# MRCS-Buckeroo.net
KiCad netlist of a schematic drawn in EAGLE
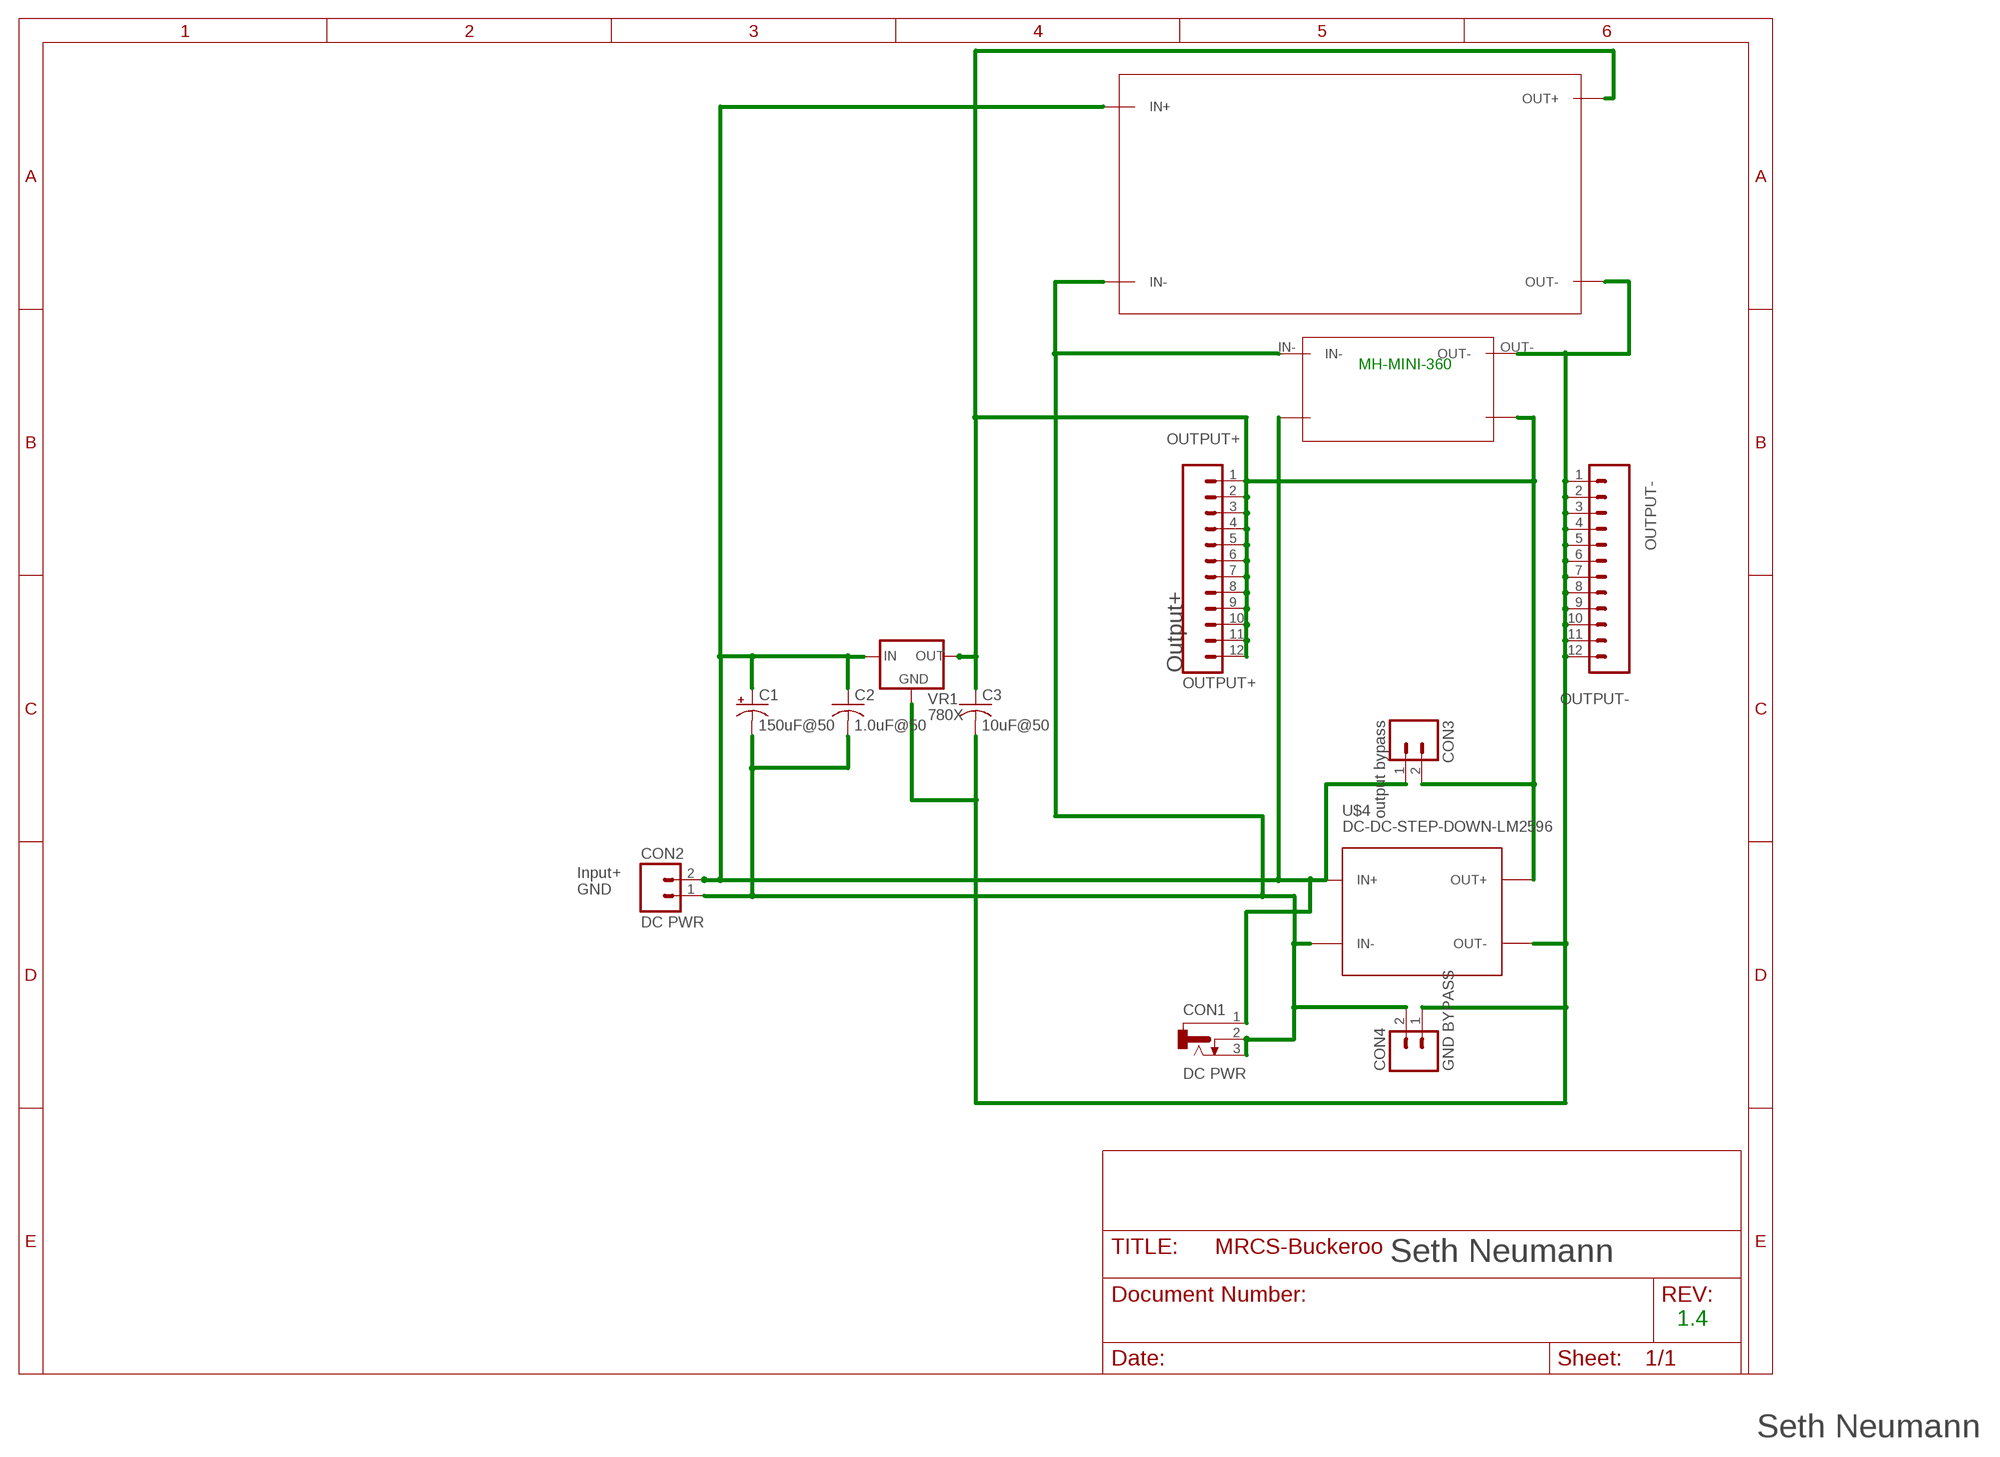
[diagram p0: schematic, sheet 1]

(export (version "E")
  (design (tool "Eeschema 10.0.6"))
  (components
    (comp (ref "C1")
      (value "150uF@50")
      (footprint "eagle-import:E5-10.5")
      (libsource (lib "eagle-import") (part "CAP-POLPTH-5MM"))
    )
    (comp (ref "C2")
      (value "1.0uF@50")
      (footprint "eagle-import:C-PTH-0.100")
      (libsource (lib "eagle-import") (part "CAPPTH2"))
    )
    (comp (ref "C3")
      (value "10uF@50")
      (footprint "eagle-import:C-PTH-0.100")
      (libsource (lib "eagle-import") (part "CAPPTH2"))
    )
    (comp (ref "CON1")
      (value "DC PWR")
      (footprint "eagle-import:DCJ0202")
      (libsource (lib "eagle-import") (part "CONNECTOR-DC-POWER-RA"))
    )
    (comp (ref "CON2")
      (value "DC PWR")
      (footprint "eagle-import:SCREWTERMINAL-3.5MM-2_LOCK")
      (libsource (lib "eagle-import") (part "CONNECTOR-M023.5MM-LOCK"))
    )
    (comp (ref "CON3")
      (value "output bypass")
      (footprint "eagle-import:MOLEX-1X2_LOCK")
      (libsource (lib "eagle-import") (part "CONNECTOR-M02MOLEX-1X02-LOCK"))
    )
    (comp (ref "CON4")
      (value "GND BYPASS")
      (footprint "eagle-import:MOLEX-1X2_LOCK")
      (libsource (lib "eagle-import") (part "CONNECTOR-M02MOLEX-1X02-LOCK"))
    )
    (comp (ref "MH-MINI-360")
      (value "MH-MINI-360")
      (footprint "eagle-import:MH-MINI-360")
      (libsource (lib "eagle-import") (part "MH-MINI-360"))
    )
    (comp (ref "OUTPUT+")
      (value "OUTPUT+")
      (footprint "eagle-import:1X12_LOCK")
      (libsource (lib "eagle-import") (part "CONNECTOR-M12LOCK"))
    )
    (comp (ref "OUTPUT-")
      (value "OUTPUT-")
      (footprint "eagle-import:1X12_LOCK")
      (libsource (lib "eagle-import") (part "CONNECTOR-M12LOCK"))
    )
    (comp (ref "U$4")
      (value "DC-DC-STEP-DOWN-LM2596")
      (footprint "eagle-import:DC-DC-STEP-DOWN-LM2596")
      (libsource (lib "eagle-import") (part "DC-DC-STEP-DOWN-LM2596"))
    )
    (comp (ref "U$5")
      (value "XL6009BOARD")
      (footprint "eagle-import:XL6009_BOARD")
      (libsource (lib "eagle-import") (part "XL6009BOARD"))
    )
    (comp (ref "VR1")
      (value "780X")
      (footprint "eagle-import:TO-220-RA")
      (libsource (lib "eagle-import") (part "VREG-?-PTH-RA"))
    )
  )
  (nets
    (net (code "1") (name "Net-(CON2-A)") (class "Default")
      (node (ref "C1") (pin "-") (pinfunction "-_-") (pintype "passive"))
      (node (ref "C2") (pin "2") (pinfunction "2_2") (pintype "passive"))
      (node (ref "CON1") (pin "2") (pinfunction "2_2") (pintype "passive"))
      (node (ref "CON1") (pin "3") (pinfunction "3_3") (pintype "passive"))
      (node (ref "CON2") (pin "1") (pinfunction "A_1") (pintype "passive"))
      (node (ref "CON4") (pin "2") (pinfunction "B_2") (pintype "passive"))
      (node (ref "MH-MINI-360") (pin "IN-") (pinfunction "IN-_IN-") (pintype "bidirectional"))
      (node (ref "U$4") (pin "IN-") (pinfunction "IN-_IN-") (pintype "bidirectional"))
      (node (ref "U$5") (pin "IN-") (pinfunction "IN-_IN-") (pintype "bidirectional"))
    )
    (net (code "2") (name "Net-(CON2-B)") (class "Default")
      (node (ref "C1") (pin "+") (pinfunction "+_+") (pintype "passive"))
      (node (ref "C2") (pin "1") (pinfunction "1_1") (pintype "passive"))
      (node (ref "CON1") (pin "1") (pinfunction "1_1") (pintype "passive"))
      (node (ref "CON2") (pin "2") (pinfunction "B_2") (pintype "passive"))
      (node (ref "CON3") (pin "1") (pinfunction "A_1") (pintype "passive"))
      (node (ref "MH-MINI-360") (pin "INN+") (pinfunction "INN+_INN+") (pintype "bidirectional"))
      (node (ref "U$4") (pin "IN+") (pinfunction "IN+_IN+") (pintype "bidirectional"))
      (node (ref "U$5") (pin "IN+") (pinfunction "IN+_IN+") (pintype "bidirectional"))
      (node (ref "VR1") (pin "IN") (pinfunction "IN_IN") (pintype "input"))
    )
    (net (code "3") (name "Net-(CON3-B)") (class "Default")
      (node (ref "C3") (pin "1") (pinfunction "1_1") (pintype "passive"))
      (node (ref "CON3") (pin "2") (pinfunction "B_2") (pintype "passive"))
      (node (ref "MH-MINI-360") (pin "OUTT+") (pinfunction "OUTT+_OUTT+") (pintype "bidirectional"))
      (node (ref "OUTPUT+") (pin "1") (pinfunction "1_1") (pintype "passive"))
      (node (ref "OUTPUT+") (pin "10") (pinfunction "10_10") (pintype "passive"))
      (node (ref "OUTPUT+") (pin "11") (pinfunction "11_11") (pintype "passive"))
      (node (ref "OUTPUT+") (pin "12") (pinfunction "12_12") (pintype "passive"))
      (node (ref "OUTPUT+") (pin "2") (pinfunction "2_2") (pintype "passive"))
      (node (ref "OUTPUT+") (pin "3") (pinfunction "3_3") (pintype "passive"))
      (node (ref "OUTPUT+") (pin "4") (pinfunction "4_4") (pintype "passive"))
      (node (ref "OUTPUT+") (pin "5") (pinfunction "5_5") (pintype "passive"))
      (node (ref "OUTPUT+") (pin "6") (pinfunction "6_6") (pintype "passive"))
      (node (ref "OUTPUT+") (pin "7") (pinfunction "7_7") (pintype "passive"))
      (node (ref "OUTPUT+") (pin "8") (pinfunction "8_8") (pintype "passive"))
      (node (ref "OUTPUT+") (pin "9") (pinfunction "9_9") (pintype "passive"))
      (node (ref "U$4") (pin "OUT+") (pinfunction "OUT+_OUT+") (pintype "bidirectional"))
      (node (ref "U$5") (pin "OUT+") (pinfunction "OUT+_OUT+") (pintype "bidirectional"))
      (node (ref "VR1") (pin "OUT") (pinfunction "OUT_OUT") (pintype "output"))
    )
    (net (code "4") (name "Net-(CON4-A)") (class "Default")
      (node (ref "C3") (pin "2") (pinfunction "2_2") (pintype "passive"))
      (node (ref "CON4") (pin "1") (pinfunction "A_1") (pintype "passive"))
      (node (ref "MH-MINI-360") (pin "OUT-") (pinfunction "OUT-_OUT-") (pintype "bidirectional"))
      (node (ref "OUTPUT-") (pin "1") (pinfunction "1_1") (pintype "passive"))
      (node (ref "OUTPUT-") (pin "10") (pinfunction "10_10") (pintype "passive"))
      (node (ref "OUTPUT-") (pin "11") (pinfunction "11_11") (pintype "passive"))
      (node (ref "OUTPUT-") (pin "12") (pinfunction "12_12") (pintype "passive"))
      (node (ref "OUTPUT-") (pin "2") (pinfunction "2_2") (pintype "passive"))
      (node (ref "OUTPUT-") (pin "3") (pinfunction "3_3") (pintype "passive"))
      (node (ref "OUTPUT-") (pin "4") (pinfunction "4_4") (pintype "passive"))
      (node (ref "OUTPUT-") (pin "5") (pinfunction "5_5") (pintype "passive"))
      (node (ref "OUTPUT-") (pin "6") (pinfunction "6_6") (pintype "passive"))
      (node (ref "OUTPUT-") (pin "7") (pinfunction "7_7") (pintype "passive"))
      (node (ref "OUTPUT-") (pin "8") (pinfunction "8_8") (pintype "passive"))
      (node (ref "OUTPUT-") (pin "9") (pinfunction "9_9") (pintype "passive"))
      (node (ref "U$4") (pin "OUT-") (pinfunction "OUT-_OUT-") (pintype "bidirectional"))
      (node (ref "U$5") (pin "OUT-") (pinfunction "OUT-_OUT-") (pintype "bidirectional"))
      (node (ref "VR1") (pin "GND") (pinfunction "GND_GND") (pintype "input"))
    )
  )
)
